# 2p_behavior.net
KiCad netlist of a schematic drawn in EAGLE
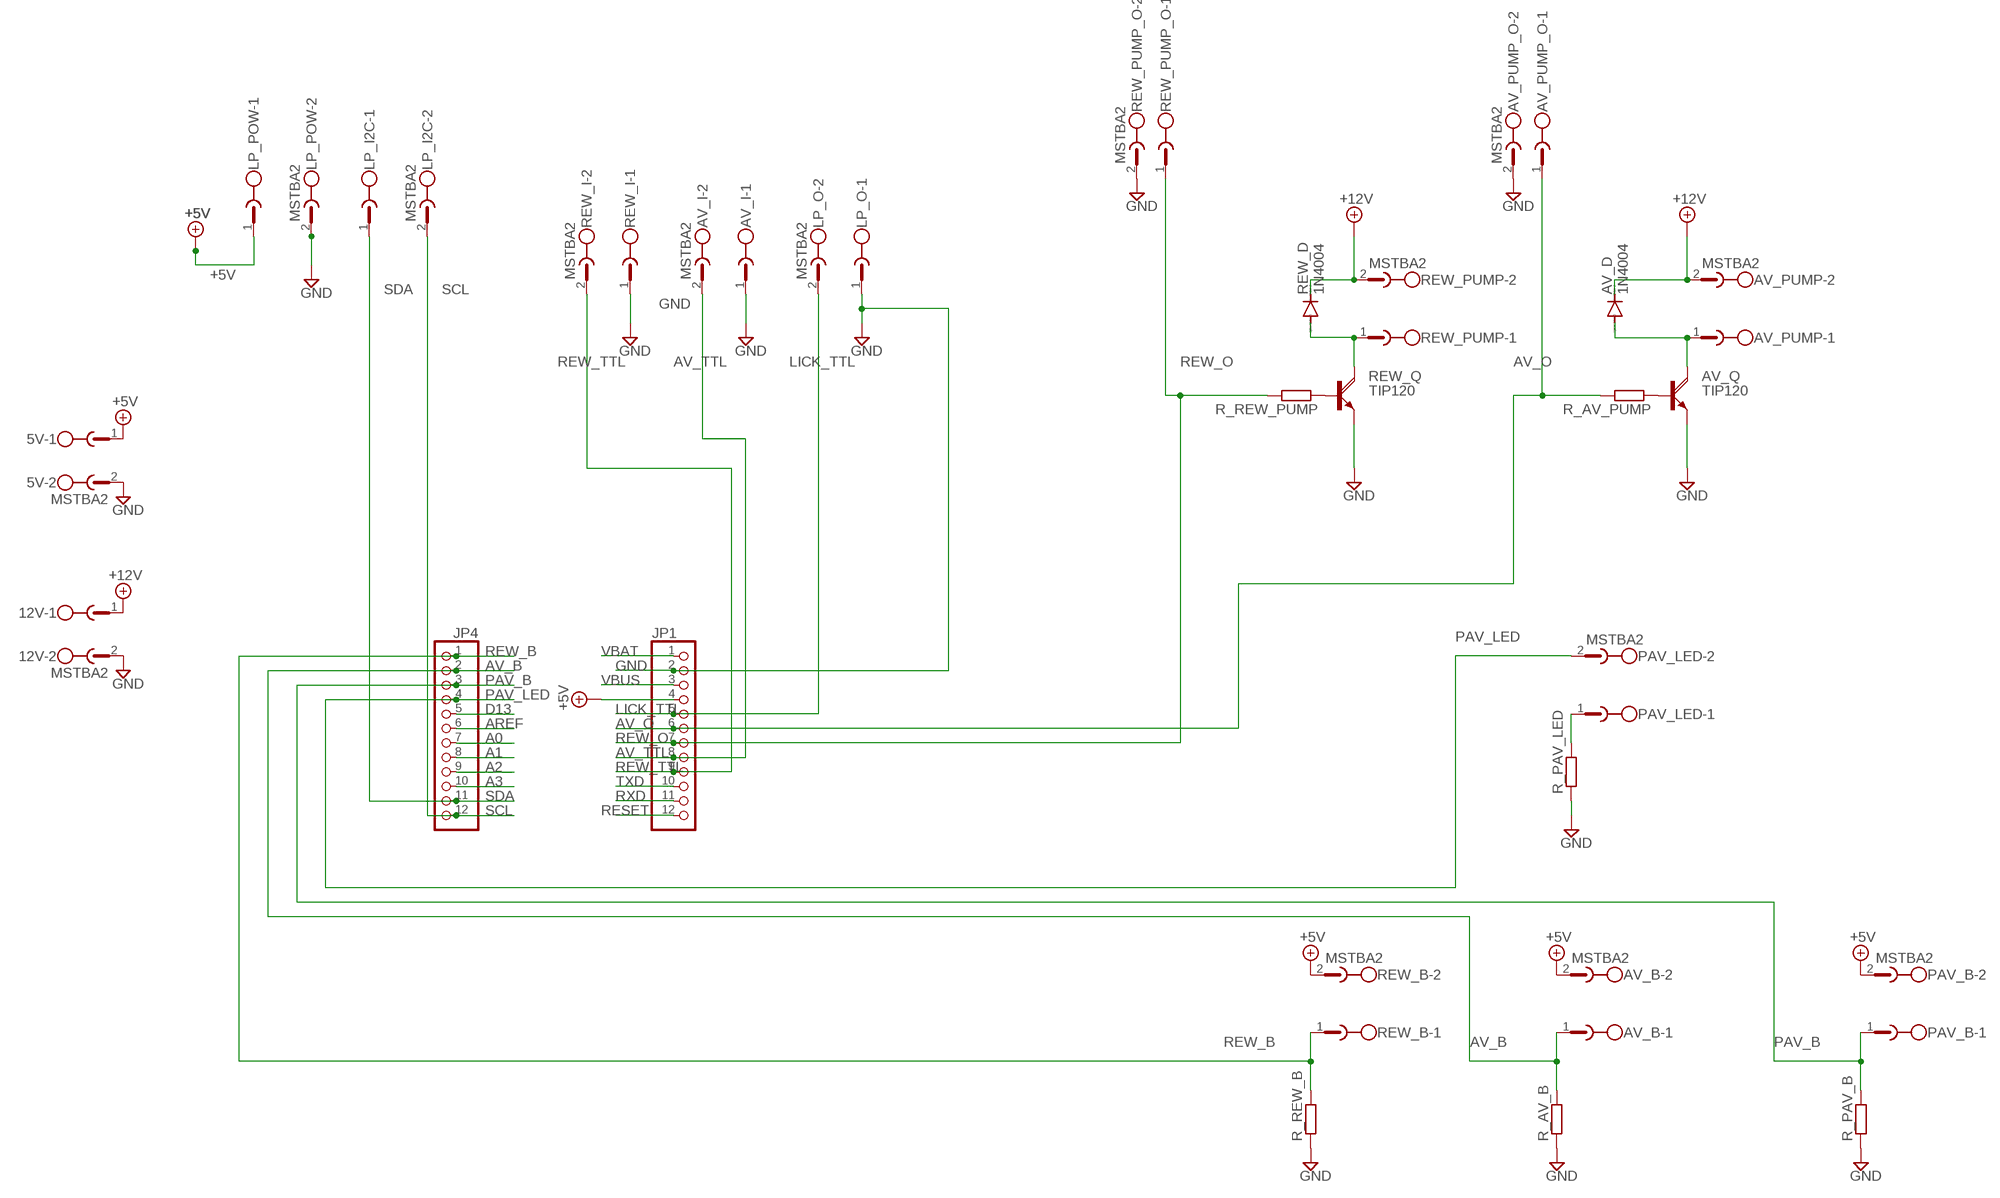
[diagram p0: schematic, sheet 1]

(export (version "E")
  (design (tool "Eeschema 10.0.6"))
  (components
    (comp (ref "5V")
      (value "MSTBA2")
      (footprint "eagle-import:MSTBA2")
      (fields (field (name "MF") "FARNELL") (field (name "MPN") "1757242"))
      (libsource (lib "eagle-import") (part "MSTBA2"))
    )
    (comp (ref "12V")
      (value "MSTBA2")
      (footprint "eagle-import:MSTBA2")
      (fields (field (name "MF") "FARNELL") (field (name "MPN") "1757242"))
      (libsource (lib "eagle-import") (part "MSTBA2"))
    )
    (comp (ref "AV_B")
      (value "MSTBA2")
      (footprint "eagle-import:MSTBA2")
      (fields (field (name "MF") "FARNELL") (field (name "MPN") "1757242"))
      (libsource (lib "eagle-import") (part "MSTBA2"))
    )
    (comp (ref "AV_D")
      (value "1N4004")
      (footprint "eagle-import:DO41-10")
      (libsource (lib "eagle-import") (part "1N4004"))
    )
    (comp (ref "AV_I")
      (value "MSTBA2")
      (footprint "eagle-import:MSTBA2")
      (fields (field (name "MF") "FARNELL") (field (name "MPN") "1757242"))
      (libsource (lib "eagle-import") (part "MSTBA2"))
    )
    (comp (ref "AV_PUMP")
      (value "MSTBA2")
      (footprint "eagle-import:MSTBA2")
      (fields (field (name "MF") "FARNELL") (field (name "MPN") "1757242"))
      (libsource (lib "eagle-import") (part "MSTBA2"))
    )
    (comp (ref "AV_PUMP_O")
      (value "MSTBA2")
      (footprint "eagle-import:MSTBA2")
      (fields (field (name "MF") "FARNELL") (field (name "MPN") "1757242"))
      (libsource (lib "eagle-import") (part "MSTBA2"))
    )
    (comp (ref "AV_Q")
      (value "TIP120")
      (footprint "eagle-import:TO220AH")
      (libsource (lib "eagle-import") (part "TIP120"))
    )
    (comp (ref "JP1")
      (value "PINHD-1X12-CB")
      (footprint "eagle-import:1X12-CB")
      (libsource (lib "eagle-import") (part "PINHD-1X12-CB"))
    )
    (comp (ref "JP4")
      (value "PINHD-1X12-CB")
      (footprint "eagle-import:1X12-CB")
      (libsource (lib "eagle-import") (part "PINHD-1X12-CB"))
    )
    (comp (ref "LP_I2C")
      (value "MSTBA2")
      (footprint "eagle-import:MSTBA2")
      (fields (field (name "MF") "FARNELL") (field (name "MPN") "1757242"))
      (libsource (lib "eagle-import") (part "MSTBA2"))
    )
    (comp (ref "LP_O")
      (value "MSTBA2")
      (footprint "eagle-import:MSTBA2")
      (fields (field (name "MF") "FARNELL") (field (name "MPN") "1757242"))
      (libsource (lib "eagle-import") (part "MSTBA2"))
    )
    (comp (ref "LP_POW")
      (value "MSTBA2")
      (footprint "eagle-import:MSTBA2")
      (fields (field (name "MF") "FARNELL") (field (name "MPN") "1757242"))
      (libsource (lib "eagle-import") (part "MSTBA2"))
    )
    (comp (ref "PAV_B")
      (value "MSTBA2")
      (footprint "eagle-import:MSTBA2")
      (fields (field (name "MF") "FARNELL") (field (name "MPN") "1757242"))
      (libsource (lib "eagle-import") (part "MSTBA2"))
    )
    (comp (ref "PAV_LED")
      (value "MSTBA2")
      (footprint "eagle-import:MSTBA2")
      (fields (field (name "MF") "FARNELL") (field (name "MPN") "1757242"))
      (libsource (lib "eagle-import") (part "MSTBA2"))
    )
    (comp (ref "REW_B")
      (value "MSTBA2")
      (footprint "eagle-import:MSTBA2")
      (fields (field (name "MF") "FARNELL") (field (name "MPN") "1757242"))
      (libsource (lib "eagle-import") (part "MSTBA2"))
    )
    (comp (ref "REW_D")
      (value "1N4004")
      (footprint "eagle-import:DO41-10")
      (libsource (lib "eagle-import") (part "1N4004"))
    )
    (comp (ref "REW_I")
      (value "MSTBA2")
      (footprint "eagle-import:MSTBA2")
      (fields (field (name "MF") "FARNELL") (field (name "MPN") "1757242"))
      (libsource (lib "eagle-import") (part "MSTBA2"))
    )
    (comp (ref "REW_PUMP")
      (value "MSTBA2")
      (footprint "eagle-import:MSTBA2")
      (fields (field (name "MF") "FARNELL") (field (name "MPN") "1757242"))
      (libsource (lib "eagle-import") (part "MSTBA2"))
    )
    (comp (ref "REW_PUMP_O")
      (value "MSTBA2")
      (footprint "eagle-import:MSTBA2")
      (fields (field (name "MF") "FARNELL") (field (name "MPN") "1757242"))
      (libsource (lib "eagle-import") (part "MSTBA2"))
    )
    (comp (ref "REW_Q")
      (value "TIP120")
      (footprint "eagle-import:TO220AH")
      (libsource (lib "eagle-import") (part "TIP120"))
    )
    (comp (ref "R_AV_B")
      (value "R-EU_0207/5V")
      (footprint "eagle-import:0207_5V")
      (libsource (lib "eagle-import") (part "R-EU_0207/5V"))
    )
    (comp (ref "R_AV_PUMP")
      (value "R-EU_0207/5V")
      (footprint "eagle-import:0207_5V")
      (libsource (lib "eagle-import") (part "R-EU_0207/5V"))
    )
    (comp (ref "R_PAV_B")
      (value "R-EU_0207/5V")
      (footprint "eagle-import:0207_5V")
      (libsource (lib "eagle-import") (part "R-EU_0207/5V"))
    )
    (comp (ref "R_PAV_LED")
      (value "R-EU_0207/5V")
      (footprint "eagle-import:0207_5V")
      (libsource (lib "eagle-import") (part "R-EU_0207/5V"))
    )
    (comp (ref "R_REW_B")
      (value "R-EU_0207/5V")
      (footprint "eagle-import:0207_5V")
      (libsource (lib "eagle-import") (part "R-EU_0207/5V"))
    )
    (comp (ref "R_REW_PUMP")
      (value "R-EU_0207/5V")
      (footprint "eagle-import:0207_5V")
      (libsource (lib "eagle-import") (part "R-EU_0207/5V"))
    )
  )
  (nets
    (net (code "1") (name "+5V") (class "Default")
      (node (ref "5V") (pin "1") (pinfunction "1_1") (pintype "passive"))
      (node (ref "AV_B") (pin "2") (pinfunction "1_2") (pintype "passive"))
      (node (ref "JP1") (pin "4") (pinfunction "4_4") (pintype "passive"))
      (node (ref "LP_POW") (pin "1") (pinfunction "1_1") (pintype "passive"))
      (node (ref "PAV_B") (pin "2") (pinfunction "1_2") (pintype "passive"))
      (node (ref "REW_B") (pin "2") (pinfunction "1_2") (pintype "passive"))
    )
    (net (code "2") (name "+12V") (class "Default")
      (node (ref "12V") (pin "1") (pinfunction "1_1") (pintype "passive"))
      (node (ref "AV_D") (pin "C") (pinfunction "C_C") (pintype "passive"))
      (node (ref "AV_PUMP") (pin "2") (pinfunction "1_2") (pintype "passive"))
      (node (ref "REW_D") (pin "C") (pinfunction "C_C") (pintype "passive"))
      (node (ref "REW_PUMP") (pin "2") (pinfunction "1_2") (pintype "passive"))
    )
    (net (code "3") (name "/A0") (class "Default")
      (node (ref "JP4") (pin "7") (pinfunction "7_7") (pintype "passive"))
    )
    (net (code "4") (name "/A1") (class "Default")
      (node (ref "JP4") (pin "8") (pinfunction "8_8") (pintype "passive"))
    )
    (net (code "5") (name "/A2") (class "Default")
      (node (ref "JP4") (pin "9") (pinfunction "9_9") (pintype "passive"))
    )
    (net (code "6") (name "/A3") (class "Default")
      (node (ref "JP4") (pin "10") (pinfunction "10_10") (pintype "passive"))
    )
    (net (code "7") (name "/AREF") (class "Default")
      (node (ref "JP4") (pin "6") (pinfunction "6_6") (pintype "passive"))
    )
    (net (code "8") (name "/AV_B") (class "Default")
      (node (ref "AV_B") (pin "1") (pinfunction "1_1") (pintype "passive"))
      (node (ref "JP4") (pin "2") (pinfunction "2_2") (pintype "passive"))
      (node (ref "R_AV_B") (pin "2") (pinfunction "2_2") (pintype "passive"))
    )
    (net (code "9") (name "/AV_O") (class "Default")
      (node (ref "AV_PUMP_O") (pin "1") (pinfunction "1_1") (pintype "passive"))
      (node (ref "JP1") (pin "6") (pinfunction "6_6") (pintype "passive"))
      (node (ref "R_AV_PUMP") (pin "2") (pinfunction "2_2") (pintype "passive"))
    )
    (net (code "10") (name "/AV_TTL") (class "Default")
      (node (ref "AV_I") (pin "2") (pinfunction "1_2") (pintype "passive"))
      (node (ref "JP1") (pin "8") (pinfunction "8_8") (pintype "passive"))
    )
    (net (code "11") (name "/D13") (class "Default")
      (node (ref "JP4") (pin "5") (pinfunction "5_5") (pintype "passive"))
    )
    (net (code "12") (name "/LICK_TTL") (class "Default")
      (node (ref "JP1") (pin "5") (pinfunction "5_5") (pintype "passive"))
      (node (ref "LP_O") (pin "2") (pinfunction "1_2") (pintype "passive"))
    )
    (net (code "13") (name "/PAV_B") (class "Default")
      (node (ref "JP4") (pin "3") (pinfunction "3_3") (pintype "passive"))
      (node (ref "PAV_B") (pin "1") (pinfunction "1_1") (pintype "passive"))
      (node (ref "R_PAV_B") (pin "2") (pinfunction "2_2") (pintype "passive"))
    )
    (net (code "14") (name "/PAV_LED") (class "Default")
      (node (ref "JP4") (pin "4") (pinfunction "4_4") (pintype "passive"))
      (node (ref "PAV_LED") (pin "2") (pinfunction "1_2") (pintype "passive"))
    )
    (net (code "15") (name "/RESET") (class "Default")
      (node (ref "JP1") (pin "12") (pinfunction "12_12") (pintype "passive"))
    )
    (net (code "16") (name "/REW_B") (class "Default")
      (node (ref "JP4") (pin "1") (pinfunction "1_1") (pintype "passive"))
      (node (ref "REW_B") (pin "1") (pinfunction "1_1") (pintype "passive"))
      (node (ref "R_REW_B") (pin "2") (pinfunction "2_2") (pintype "passive"))
    )
    (net (code "17") (name "/REW_O") (class "Default")
      (node (ref "JP1") (pin "7") (pinfunction "7_7") (pintype "passive"))
      (node (ref "REW_PUMP_O") (pin "1") (pinfunction "1_1") (pintype "passive"))
      (node (ref "R_REW_PUMP") (pin "2") (pinfunction "2_2") (pintype "passive"))
    )
    (net (code "18") (name "/REW_TTL") (class "Default")
      (node (ref "JP1") (pin "9") (pinfunction "9_9") (pintype "passive"))
      (node (ref "REW_I") (pin "2") (pinfunction "1_2") (pintype "passive"))
    )
    (net (code "19") (name "/RXD") (class "Default")
      (node (ref "JP1") (pin "11") (pinfunction "11_11") (pintype "passive"))
    )
    (net (code "20") (name "/SCL") (class "Default")
      (node (ref "JP4") (pin "12") (pinfunction "12_12") (pintype "passive"))
      (node (ref "LP_I2C") (pin "2") (pinfunction "1_2") (pintype "passive"))
    )
    (net (code "21") (name "/SDA") (class "Default")
      (node (ref "JP4") (pin "11") (pinfunction "11_11") (pintype "passive"))
      (node (ref "LP_I2C") (pin "1") (pinfunction "1_1") (pintype "passive"))
    )
    (net (code "22") (name "/TXD") (class "Default")
      (node (ref "JP1") (pin "10") (pinfunction "10_10") (pintype "passive"))
    )
    (net (code "23") (name "/VBAT") (class "Default")
      (node (ref "JP1") (pin "1") (pinfunction "1_1") (pintype "passive"))
    )
    (net (code "24") (name "/VBUS") (class "Default")
      (node (ref "JP1") (pin "3") (pinfunction "3_3") (pintype "passive"))
    )
    (net (code "25") (name "GND") (class "Default")
      (node (ref "12V") (pin "2") (pinfunction "1_2") (pintype "passive"))
      (node (ref "5V") (pin "2") (pinfunction "1_2") (pintype "passive"))
      (node (ref "AV_I") (pin "1") (pinfunction "1_1") (pintype "passive"))
      (node (ref "AV_PUMP_O") (pin "2") (pinfunction "1_2") (pintype "passive"))
      (node (ref "AV_Q") (pin "E") (pinfunction "E_E") (pintype "passive"))
      (node (ref "JP1") (pin "2") (pinfunction "2_2") (pintype "passive"))
      (node (ref "LP_O") (pin "1") (pinfunction "1_1") (pintype "passive"))
      (node (ref "LP_POW") (pin "2") (pinfunction "1_2") (pintype "passive"))
      (node (ref "REW_I") (pin "1") (pinfunction "1_1") (pintype "passive"))
      (node (ref "REW_PUMP_O") (pin "2") (pinfunction "1_2") (pintype "passive"))
      (node (ref "REW_Q") (pin "E") (pinfunction "E_E") (pintype "passive"))
      (node (ref "R_AV_B") (pin "1") (pinfunction "1_1") (pintype "passive"))
      (node (ref "R_PAV_B") (pin "1") (pinfunction "1_1") (pintype "passive"))
      (node (ref "R_PAV_LED") (pin "1") (pinfunction "1_1") (pintype "passive"))
      (node (ref "R_REW_B") (pin "1") (pinfunction "1_1") (pintype "passive"))
    )
    (net (code "26") (name "Net-(AV_D-PadA)") (class "Default")
      (node (ref "AV_D") (pin "A") (pinfunction "A_A") (pintype "passive"))
      (node (ref "AV_PUMP") (pin "1") (pinfunction "1_1") (pintype "passive"))
      (node (ref "AV_Q") (pin "C") (pinfunction "C_C") (pintype "passive"))
    )
    (net (code "27") (name "Net-(AV_Q-PadB)") (class "Default")
      (node (ref "AV_Q") (pin "B") (pinfunction "B_B") (pintype "passive"))
      (node (ref "R_AV_PUMP") (pin "1") (pinfunction "1_1") (pintype "passive"))
    )
    (net (code "28") (name "Net-(PAV_LED-Pad1)") (class "Default")
      (node (ref "PAV_LED") (pin "1") (pinfunction "1_1") (pintype "passive"))
      (node (ref "R_PAV_LED") (pin "2") (pinfunction "2_2") (pintype "passive"))
    )
    (net (code "29") (name "Net-(REW_D-PadA)") (class "Default")
      (node (ref "REW_D") (pin "A") (pinfunction "A_A") (pintype "passive"))
      (node (ref "REW_PUMP") (pin "1") (pinfunction "1_1") (pintype "passive"))
      (node (ref "REW_Q") (pin "C") (pinfunction "C_C") (pintype "passive"))
    )
    (net (code "30") (name "Net-(REW_Q-PadB)") (class "Default")
      (node (ref "REW_Q") (pin "B") (pinfunction "B_B") (pintype "passive"))
      (node (ref "R_REW_PUMP") (pin "1") (pinfunction "1_1") (pintype "passive"))
    )
  )
)
